# RELIP_reader_withoutVias.net
KiCad netlist of a schematic drawn in EAGLE
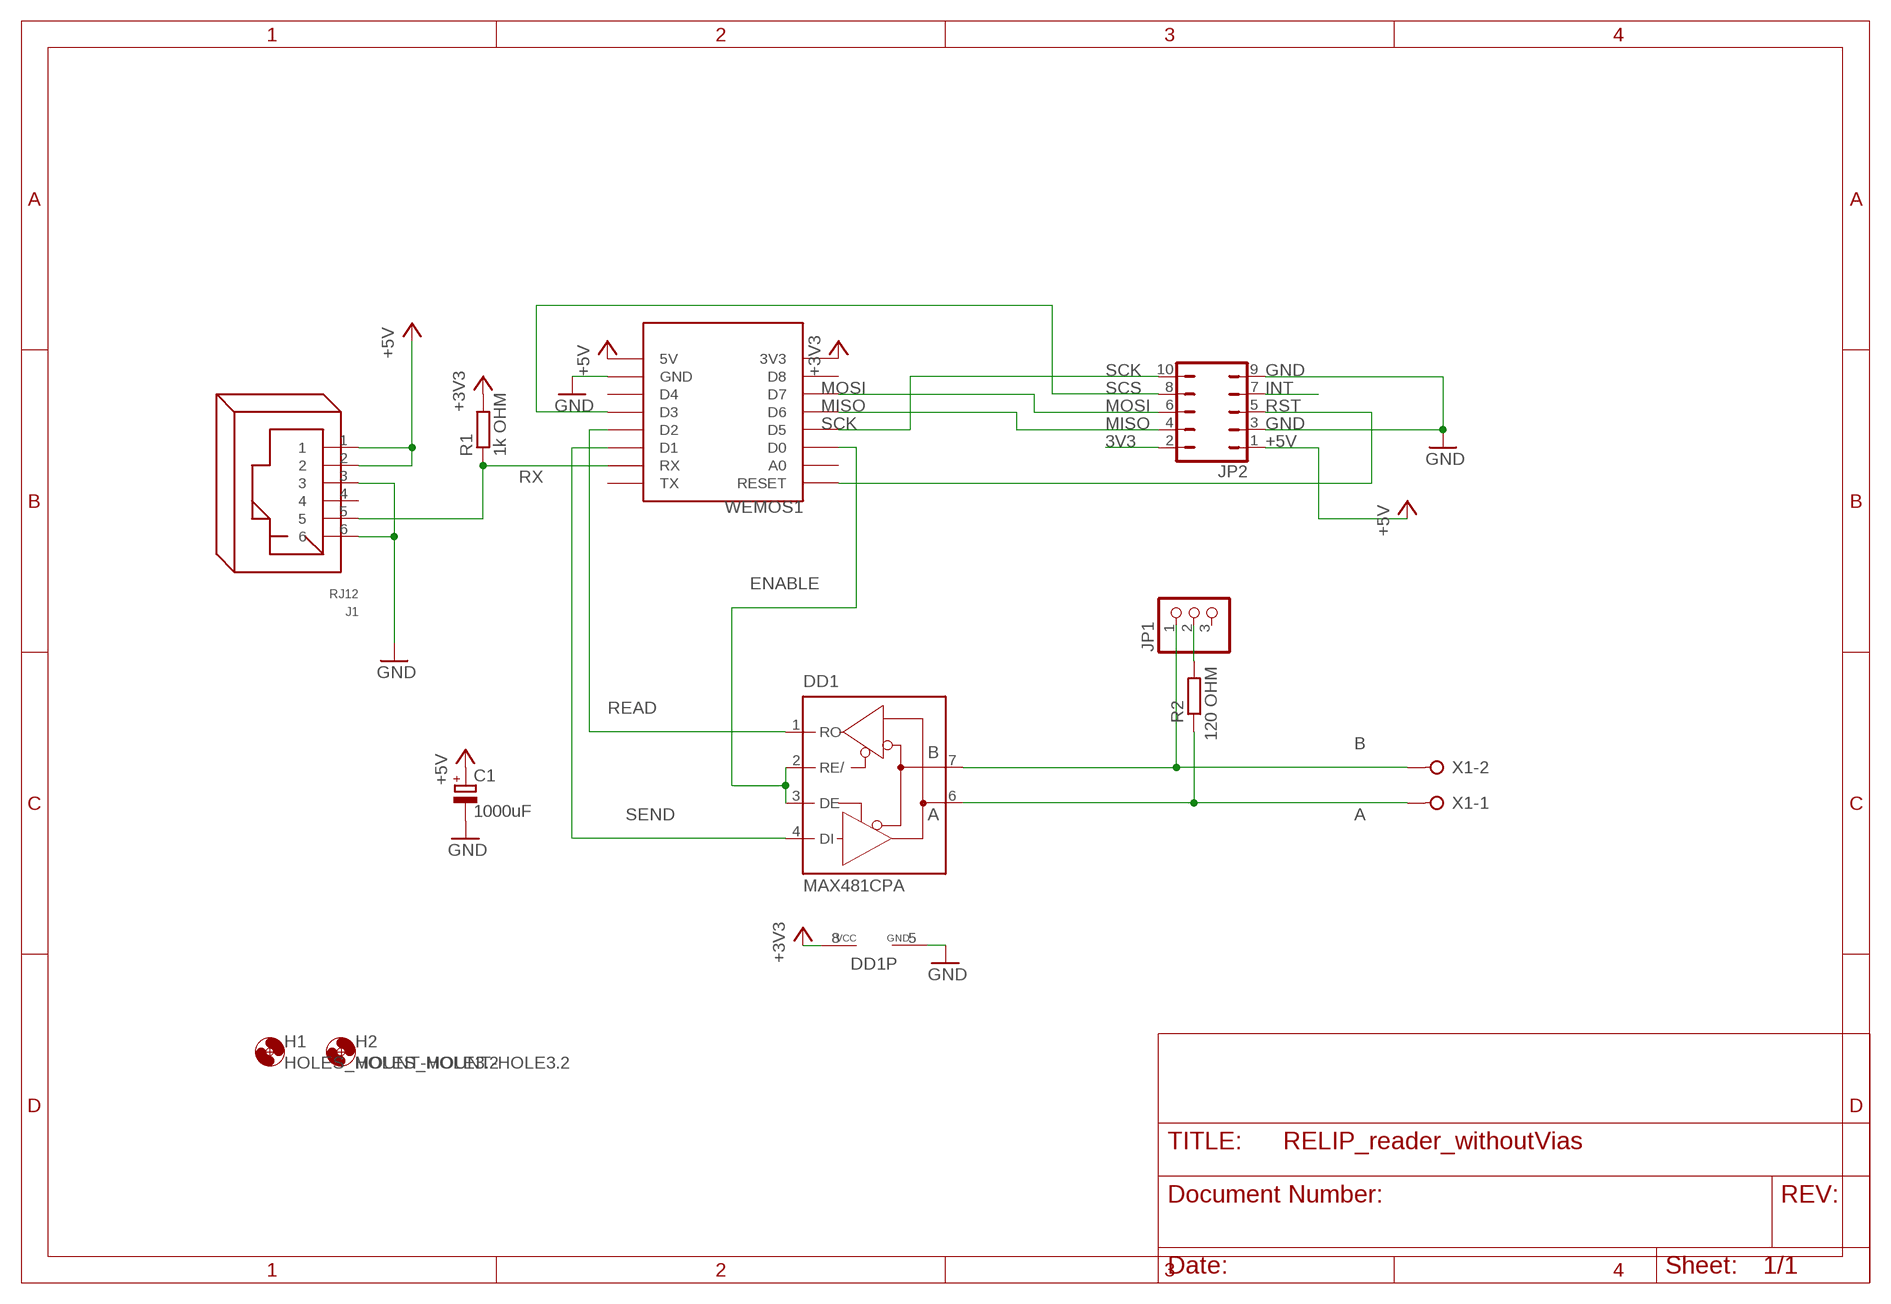
[diagram p0: schematic, sheet 1]

(export (version "E")
  (design (tool "Eeschema 10.0.6"))
  (components
    (comp (ref "C1")
      (value "1000uF")
      (footprint "eagle-import:E3,5-8")
      (libsource (lib "eagle-import") (part "CPOL-EUE3.5-8"))
    )
    (comp (ref "DD1")
      (value "MAX481CPA")
      (footprint "eagle-import:DIL08")
      (libsource (lib "eagle-import") (part "MAX481CPA"))
    )
    (comp (ref "H1")
      (value "HOLES_MOUNT-HOLE3.2")
      (footprint "eagle-import:HOLES_3,2")
      (libsource (lib "eagle-import") (part "HOLES_MOUNT-HOLE3.2"))
    )
    (comp (ref "H2")
      (value "HOLES_MOUNT-HOLE3.2")
      (footprint "eagle-import:HOLES_3,2")
      (libsource (lib "eagle-import") (part "HOLES_MOUNT-HOLE3.2"))
    )
    (comp (ref "J1")
      (value "RJ12")
      (footprint "eagle-import:RJ12")
      (libsource (lib "eagle-import") (part "RJ12"))
    )
    (comp (ref "JP1")
      (value "PINHEAD_PINHD-1X3")
      (footprint "eagle-import:PINHEAD_1X03")
      (libsource (lib "eagle-import") (part "PINHEAD_PINHD-1X3"))
    )
    (comp (ref "JP2")
      (value "JP5Q")
      (footprint "eagle-import:JP5Q")
      (libsource (lib "eagle-import") (part "JP5Q"))
    )
    (comp (ref "R1")
      (value "1k OHM")
      (footprint "eagle-import:RCL_0207_12")
      (libsource (lib "eagle-import") (part "RCL_R-EU_0207/12"))
    )
    (comp (ref "R2")
      (value "120 OHM")
      (footprint "eagle-import:RCL_0207_12")
      (libsource (lib "eagle-import") (part "RCL_R-EU_0207/12"))
    )
    (comp (ref "WEMOS1")
      (value "WEMOS-D1-MINI")
      (footprint "eagle-import:WEMOS-D1-MINI")
      (libsource (lib "eagle-import") (part "WEMOS-D1-MINI"))
    )
    (comp (ref "X1")
      (value "W237-02P")
      (footprint "eagle-import:W237-132")
      (libsource (lib "eagle-import") (part "W237-02P"))
    )
  )
  (nets
    (net (code "1") (name "+3V3") (class "Default")
      (node (ref "DD1") (pin "8") (pinfunction "VCC_8") (pintype "power_in"))
      (node (ref "R1") (pin "2") (pinfunction "2_2") (pintype "passive"))
      (node (ref "WEMOS1") (pin "3V3") (pinfunction "3V3_3V3") (pintype "bidirectional"))
    )
    (net (code "2") (name "+5V") (class "Default")
      (node (ref "C1") (pin "+") (pinfunction "+_+") (pintype "passive"))
      (node (ref "J1") (pin "1") (pinfunction "1_1") (pintype "bidirectional"))
      (node (ref "J1") (pin "2") (pinfunction "2_2") (pintype "bidirectional"))
      (node (ref "JP2") (pin "1") (pinfunction "1_1") (pintype "passive"))
      (node (ref "WEMOS1") (pin "5V") (pinfunction "5V_5V") (pintype "bidirectional"))
    )
    (net (code "3") (name "/3V3") (class "Default")
      (node (ref "JP2") (pin "2") (pinfunction "2_2") (pintype "passive"))
    )
    (net (code "4") (name "/A") (class "Default")
      (node (ref "DD1") (pin "6") (pinfunction "A_6") (pintype "passive"))
      (node (ref "R2") (pin "1") (pinfunction "1_1") (pintype "passive"))
      (node (ref "X1") (pin "1") (pinfunction "KL_1") (pintype "passive"))
    )
    (net (code "5") (name "/B") (class "Default")
      (node (ref "DD1") (pin "7") (pinfunction "B_7") (pintype "passive"))
      (node (ref "JP1") (pin "1") (pinfunction "1_1") (pintype "passive"))
      (node (ref "X1") (pin "2") (pinfunction "KL_2") (pintype "passive"))
    )
    (net (code "6") (name "/ENABLE") (class "Default")
      (node (ref "DD1") (pin "2") (pinfunction "RE/_2") (pintype "input"))
      (node (ref "DD1") (pin "3") (pinfunction "DE_3") (pintype "input"))
      (node (ref "WEMOS1") (pin "D0") (pinfunction "D0_D0") (pintype "bidirectional"))
    )
    (net (code "7") (name "/INT") (class "Default")
      (node (ref "JP2") (pin "7") (pinfunction "7_7") (pintype "passive"))
    )
    (net (code "8") (name "/MISO") (class "Default")
      (node (ref "JP2") (pin "4") (pinfunction "4_4") (pintype "passive"))
      (node (ref "WEMOS1") (pin "D6") (pinfunction "D6_D6") (pintype "bidirectional"))
    )
    (net (code "9") (name "/MOSI") (class "Default")
      (node (ref "JP2") (pin "6") (pinfunction "6_6") (pintype "passive"))
      (node (ref "WEMOS1") (pin "D7") (pinfunction "D7_D7") (pintype "bidirectional"))
    )
    (net (code "10") (name "/READ") (class "Default")
      (node (ref "DD1") (pin "1") (pinfunction "RO_1") (pintype "output"))
      (node (ref "WEMOS1") (pin "D2") (pinfunction "D2_D2") (pintype "bidirectional"))
    )
    (net (code "11") (name "/RST") (class "Default")
      (node (ref "JP2") (pin "5") (pinfunction "5_5") (pintype "passive"))
      (node (ref "WEMOS1") (pin "RESET") (pinfunction "RESET_RESET") (pintype "bidirectional"))
    )
    (net (code "12") (name "/RX") (class "Default")
      (node (ref "J1") (pin "5") (pinfunction "5_5") (pintype "bidirectional"))
      (node (ref "R1") (pin "1") (pinfunction "1_1") (pintype "passive"))
      (node (ref "WEMOS1") (pin "RX") (pinfunction "RX_RX") (pintype "bidirectional"))
    )
    (net (code "13") (name "/SCK") (class "Default")
      (node (ref "JP2") (pin "10") (pinfunction "10_10") (pintype "passive"))
      (node (ref "WEMOS1") (pin "D5") (pinfunction "D5_D5") (pintype "bidirectional"))
    )
    (net (code "14") (name "/SCS") (class "Default")
      (node (ref "JP2") (pin "8") (pinfunction "8_8") (pintype "passive"))
      (node (ref "WEMOS1") (pin "D3") (pinfunction "D3_D3") (pintype "bidirectional"))
    )
    (net (code "15") (name "/SEND") (class "Default")
      (node (ref "DD1") (pin "4") (pinfunction "DI_4") (pintype "input"))
      (node (ref "WEMOS1") (pin "D1") (pinfunction "D1_D1") (pintype "bidirectional"))
    )
    (net (code "16") (name "GND") (class "Default")
      (node (ref "C1") (pin "-") (pinfunction "-_-") (pintype "passive"))
      (node (ref "DD1") (pin "5") (pinfunction "GND_5") (pintype "power_in"))
      (node (ref "J1") (pin "3") (pinfunction "3_3") (pintype "bidirectional"))
      (node (ref "J1") (pin "6") (pinfunction "6_6") (pintype "bidirectional"))
      (node (ref "JP2") (pin "3") (pinfunction "3_3") (pintype "passive"))
      (node (ref "JP2") (pin "9") (pinfunction "9_9") (pintype "passive"))
      (node (ref "WEMOS1") (pin "GND") (pinfunction "GND_GND") (pintype "bidirectional"))
    )
    (net (code "17") (name "Net-(JP1-Pad2)") (class "Default")
      (node (ref "JP1") (pin "2") (pinfunction "2_2") (pintype "passive"))
      (node (ref "R2") (pin "2") (pinfunction "2_2") (pintype "passive"))
    )
    (net (code "18") (name "unconnected-(J1-Pad4)") (class "Default")
      (node (ref "J1") (pin "4") (pinfunction "4_4") (pintype "bidirectional"))
    )
    (net (code "19") (name "unconnected-(JP1-Pad3)") (class "Default")
      (node (ref "JP1") (pin "3") (pinfunction "3_3") (pintype "passive"))
    )
    (net (code "20") (name "unconnected-(WEMOS1-PadA0)") (class "Default")
      (node (ref "WEMOS1") (pin "A0") (pinfunction "A0_A0") (pintype "bidirectional"))
    )
    (net (code "21") (name "unconnected-(WEMOS1-PadD4)") (class "Default")
      (node (ref "WEMOS1") (pin "D4") (pinfunction "D4_D4") (pintype "bidirectional"))
    )
    (net (code "22") (name "unconnected-(WEMOS1-PadD8)") (class "Default")
      (node (ref "WEMOS1") (pin "D8") (pinfunction "D8_D8") (pintype "bidirectional"))
    )
    (net (code "23") (name "unconnected-(WEMOS1-PadTX)") (class "Default")
      (node (ref "WEMOS1") (pin "TX") (pinfunction "TX_TX") (pintype "bidirectional"))
    )
  )
)
